# Arc_Reactor_v1_1.net
KiCad netlist of a schematic drawn in EAGLE
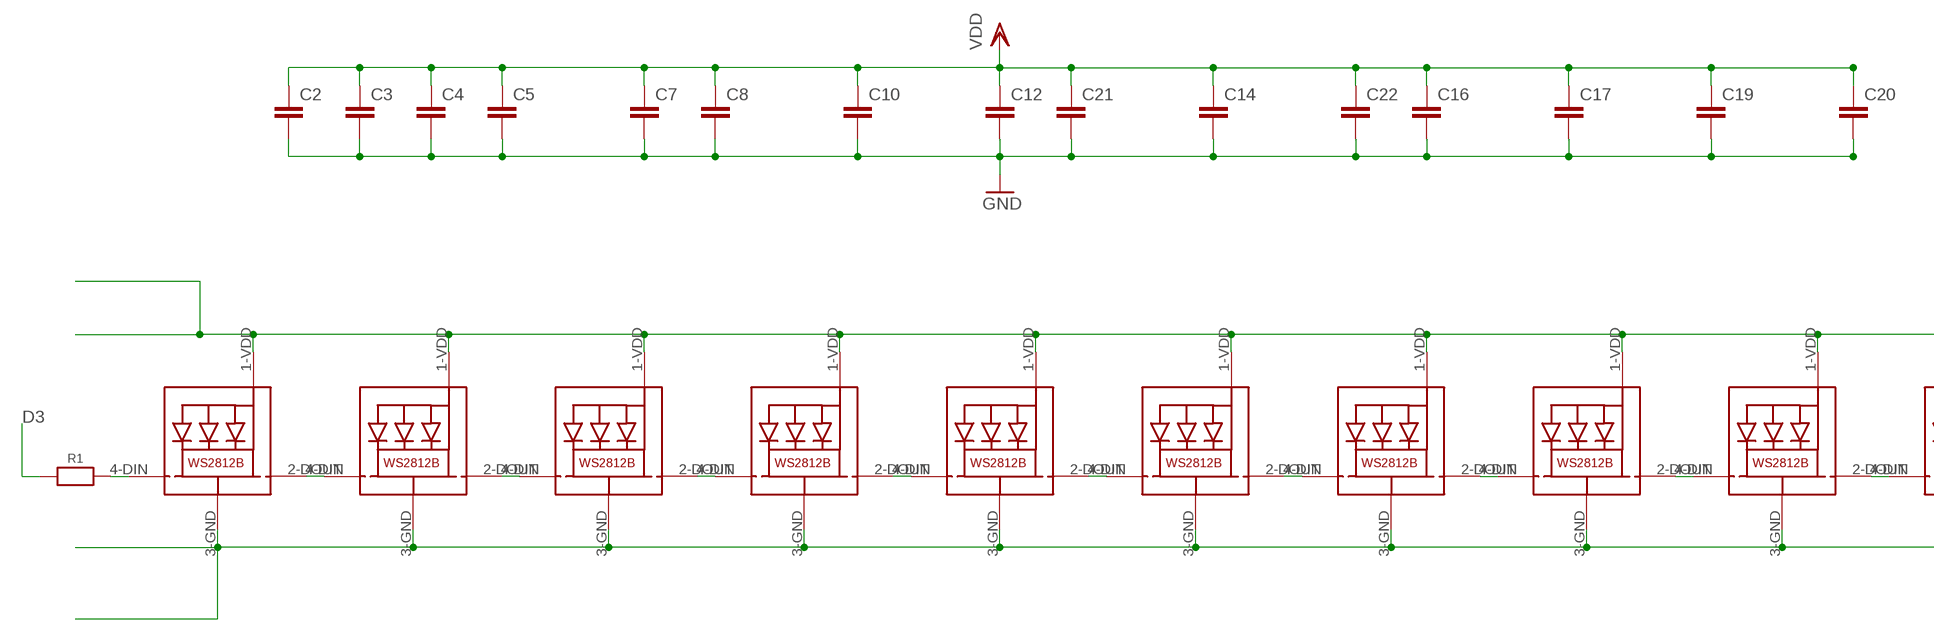
[diagram p0: schematic, sheet 1, part 1 of 2]
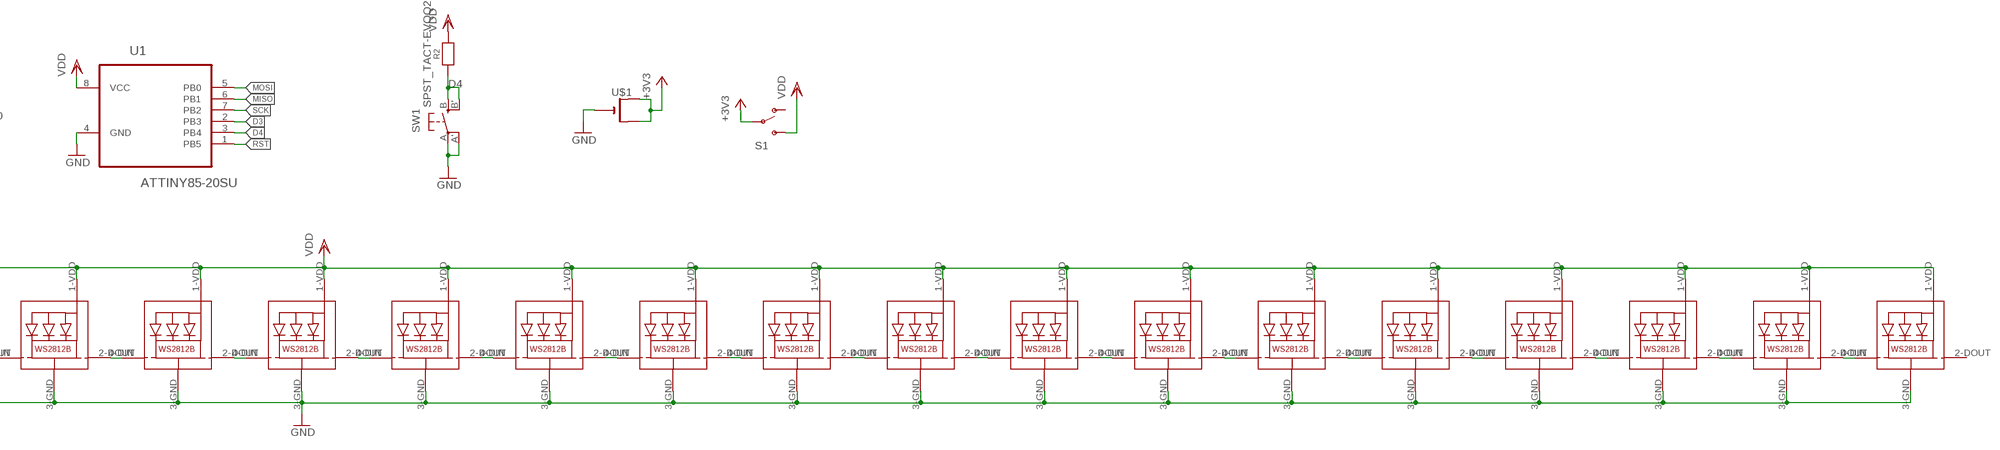
[diagram p1: schematic, sheet 1, part 2 of 2]

(export (version "E")
  (design (tool "Eeschema 10.0.6"))
  (components
    (comp (ref "C2")
      (value "C-EUC0603")
      (footprint "eagle-import:C0603")
      (libsource (lib "eagle-import") (part "C-EUC0603"))
    )
    (comp (ref "C3")
      (value "C-EUC0603")
      (footprint "eagle-import:C0603")
      (libsource (lib "eagle-import") (part "C-EUC0603"))
    )
    (comp (ref "C4")
      (value "C-EUC0603")
      (footprint "eagle-import:C0603")
      (libsource (lib "eagle-import") (part "C-EUC0603"))
    )
    (comp (ref "C5")
      (value "C-EUC0603")
      (footprint "eagle-import:C0603")
      (libsource (lib "eagle-import") (part "C-EUC0603"))
    )
    (comp (ref "C7")
      (value "C-EUC0603")
      (footprint "eagle-import:C0603")
      (libsource (lib "eagle-import") (part "C-EUC0603"))
    )
    (comp (ref "C8")
      (value "C-EUC0603")
      (footprint "eagle-import:C0603")
      (libsource (lib "eagle-import") (part "C-EUC0603"))
    )
    (comp (ref "C10")
      (value "C-EUC0603")
      (footprint "eagle-import:C0603")
      (libsource (lib "eagle-import") (part "C-EUC0603"))
    )
    (comp (ref "C12")
      (value "C-EUC0603")
      (footprint "eagle-import:C0603")
      (libsource (lib "eagle-import") (part "C-EUC0603"))
    )
    (comp (ref "C14")
      (value "C-EUC0603")
      (footprint "eagle-import:C0603")
      (libsource (lib "eagle-import") (part "C-EUC0603"))
    )
    (comp (ref "C16")
      (value "C-EUC0603")
      (footprint "eagle-import:C0603")
      (libsource (lib "eagle-import") (part "C-EUC0603"))
    )
    (comp (ref "C17")
      (value "C-EUC0603")
      (footprint "eagle-import:C0603")
      (libsource (lib "eagle-import") (part "C-EUC0603"))
    )
    (comp (ref "C19")
      (value "C-EUC0603")
      (footprint "eagle-import:C0603")
      (libsource (lib "eagle-import") (part "C-EUC0603"))
    )
    (comp (ref "C20")
      (value "C-EUC0603")
      (footprint "eagle-import:C0603")
      (libsource (lib "eagle-import") (part "C-EUC0603"))
    )
    (comp (ref "C21")
      (value "C-EUC0603")
      (footprint "eagle-import:C0603")
      (libsource (lib "eagle-import") (part "C-EUC0603"))
    )
    (comp (ref "C22")
      (value "C-EUC0603")
      (footprint "eagle-import:C0603")
      (libsource (lib "eagle-import") (part "C-EUC0603"))
    )
    (comp (ref "LED1")
      (value "WS2812B5050")
      (footprint "eagle-import:WS2812B")
      (libsource (lib "eagle-import") (part "WS2812B5050"))
    )
    (comp (ref "LED3")
      (value "WS2812B5050")
      (footprint "eagle-import:WS2812B")
      (libsource (lib "eagle-import") (part "WS2812B5050"))
    )
    (comp (ref "LED4")
      (value "WS2812B5050")
      (footprint "eagle-import:WS2812B")
      (libsource (lib "eagle-import") (part "WS2812B5050"))
    )
    (comp (ref "LED5")
      (value "WS2812B5050")
      (footprint "eagle-import:WS2812B")
      (libsource (lib "eagle-import") (part "WS2812B5050"))
    )
    (comp (ref "LED6")
      (value "WS2812B5050")
      (footprint "eagle-import:WS2812B")
      (libsource (lib "eagle-import") (part "WS2812B5050"))
    )
    (comp (ref "LED7")
      (value "WS2812B5050")
      (footprint "eagle-import:WS2812B")
      (libsource (lib "eagle-import") (part "WS2812B5050"))
    )
    (comp (ref "LED8")
      (value "WS2812B5050")
      (footprint "eagle-import:WS2812B")
      (libsource (lib "eagle-import") (part "WS2812B5050"))
    )
    (comp (ref "LED9")
      (value "WS2812B5050")
      (footprint "eagle-import:WS2812B")
      (libsource (lib "eagle-import") (part "WS2812B5050"))
    )
    (comp (ref "LED10")
      (value "WS2812B5050")
      (footprint "eagle-import:WS2812B")
      (libsource (lib "eagle-import") (part "WS2812B5050"))
    )
    (comp (ref "LED11")
      (value "WS2812B5050")
      (footprint "eagle-import:WS2812B")
      (libsource (lib "eagle-import") (part "WS2812B5050"))
    )
    (comp (ref "LED12")
      (value "WS2812B5050")
      (footprint "eagle-import:WS2812B")
      (libsource (lib "eagle-import") (part "WS2812B5050"))
    )
    (comp (ref "LED13")
      (value "WS2812B5050")
      (footprint "eagle-import:WS2812B")
      (libsource (lib "eagle-import") (part "WS2812B5050"))
    )
    (comp (ref "LED14")
      (value "WS2812B5050")
      (footprint "eagle-import:WS2812B")
      (libsource (lib "eagle-import") (part "WS2812B5050"))
    )
    (comp (ref "LED15")
      (value "WS2812B5050")
      (footprint "eagle-import:WS2812B")
      (libsource (lib "eagle-import") (part "WS2812B5050"))
    )
    (comp (ref "LED16")
      (value "WS2812B5050")
      (footprint "eagle-import:WS2812B")
      (libsource (lib "eagle-import") (part "WS2812B5050"))
    )
    (comp (ref "LED17")
      (value "WS2812B5050")
      (footprint "eagle-import:WS2812B")
      (libsource (lib "eagle-import") (part "WS2812B5050"))
    )
    (comp (ref "LED18")
      (value "WS2812B5050")
      (footprint "eagle-import:WS2812B")
      (libsource (lib "eagle-import") (part "WS2812B5050"))
    )
    (comp (ref "LED19")
      (value "WS2812B5050")
      (footprint "eagle-import:WS2812B")
      (libsource (lib "eagle-import") (part "WS2812B5050"))
    )
    (comp (ref "LED20")
      (value "WS2812B5050")
      (footprint "eagle-import:WS2812B")
      (libsource (lib "eagle-import") (part "WS2812B5050"))
    )
    (comp (ref "LED21")
      (value "WS2812B5050")
      (footprint "eagle-import:WS2812B")
      (libsource (lib "eagle-import") (part "WS2812B5050"))
    )
    (comp (ref "LED22")
      (value "WS2812B5050")
      (footprint "eagle-import:WS2812B")
      (libsource (lib "eagle-import") (part "WS2812B5050"))
    )
    (comp (ref "LED23")
      (value "WS2812B5050")
      (footprint "eagle-import:WS2812B")
      (libsource (lib "eagle-import") (part "WS2812B5050"))
    )
    (comp (ref "LED24")
      (value "WS2812B5050")
      (footprint "eagle-import:WS2812B")
      (libsource (lib "eagle-import") (part "WS2812B5050"))
    )
    (comp (ref "LED25")
      (value "WS2812B5050")
      (footprint "eagle-import:WS2812B")
      (libsource (lib "eagle-import") (part "WS2812B5050"))
    )
    (comp (ref "LED26")
      (value "WS2812B5050")
      (footprint "eagle-import:WS2812B")
      (libsource (lib "eagle-import") (part "WS2812B5050"))
    )
    (comp (ref "R1")
      (value "RESISTOR_0603_NOOUT")
      (footprint "eagle-import:0603-NO")
      (libsource (lib "eagle-import") (part "RESISTOR_0603_NOOUT"))
    )
    (comp (ref "R2")
      (value "RESISTOR_0603_NOOUT")
      (footprint "eagle-import:0603-NO")
      (libsource (lib "eagle-import") (part "RESISTOR_0603_NOOUT"))
    )
    (comp (ref "S1")
      (value "SWITCH-SPDTSMD2")
      (footprint "eagle-import:SWITCH-SPDT-SMD")
      (libsource (lib "eagle-import") (part "SWITCH-SPDTSMD2"))
    )
    (comp (ref "SW1")
      (value "SPST_TACT-EVQQ2")
      (footprint "eagle-import:EVQ-Q2")
      (libsource (lib "eagle-import") (part "SPST_TACT-EVQQ2"))
    )
    (comp (ref "U$1")
      (value "CR2032SMT")
      (footprint "eagle-import:CR2032-SMD")
      (libsource (lib "eagle-import") (part "CR2032SMT"))
    )
    (comp (ref "U1")
      (value "ATTINY85-20SU")
      (footprint "eagle-import:SOIC127P798X216-8N")
      (libsource (lib "eagle-import") (part "ATTINY85-20SU"))
    )
  )
  (nets
    (net (code "1") (name "+3V3") (class "Default")
      (node (ref "S1") (pin "2") (pinfunction "P_2") (pintype "passive"))
      (node (ref "U$1") (pin "+$1") (pinfunction "+_+$1") (pintype "passive"))
      (node (ref "U$1") (pin "+$2") (pinfunction "+1_+$2") (pintype "passive"))
    )
    (net (code "2") (name "D3") (class "Default")
      (node (ref "R1") (pin "1") (pinfunction "1_1") (pintype "passive"))
      (node (ref "U1") (pin "2") (pinfunction "PB3_2") (pintype "bidirectional"))
    )
    (net (code "3") (name "D4") (class "Default")
      (node (ref "R2") (pin "1") (pinfunction "1_1") (pintype "passive"))
      (node (ref "SW1") (pin "B") (pinfunction "S_B") (pintype "passive"))
      (node (ref "SW1") (pin "B'") (pinfunction "S1_B'") (pintype "passive"))
      (node (ref "U1") (pin "3") (pinfunction "PB4_3") (pintype "bidirectional"))
    )
    (net (code "4") (name "GND") (class "Default")
      (node (ref "C10") (pin "2") (pinfunction "2_2") (pintype "passive"))
      (node (ref "C12") (pin "2") (pinfunction "2_2") (pintype "passive"))
      (node (ref "C14") (pin "2") (pinfunction "2_2") (pintype "passive"))
      (node (ref "C16") (pin "2") (pinfunction "2_2") (pintype "passive"))
      (node (ref "C17") (pin "2") (pinfunction "2_2") (pintype "passive"))
      (node (ref "C19") (pin "2") (pinfunction "2_2") (pintype "passive"))
      (node (ref "C2") (pin "2") (pinfunction "2_2") (pintype "passive"))
      (node (ref "C20") (pin "2") (pinfunction "2_2") (pintype "passive"))
      (node (ref "C21") (pin "2") (pinfunction "2_2") (pintype "passive"))
      (node (ref "C22") (pin "2") (pinfunction "2_2") (pintype "passive"))
      (node (ref "C3") (pin "2") (pinfunction "2_2") (pintype "passive"))
      (node (ref "C4") (pin "2") (pinfunction "2_2") (pintype "passive"))
      (node (ref "C5") (pin "2") (pinfunction "2_2") (pintype "passive"))
      (node (ref "C7") (pin "2") (pinfunction "2_2") (pintype "passive"))
      (node (ref "C8") (pin "2") (pinfunction "2_2") (pintype "passive"))
      (node (ref "LED1") (pin "3-GND") (pinfunction "GND_3-GND") (pintype "power_in"))
      (node (ref "LED10") (pin "3-GND") (pinfunction "GND_3-GND") (pintype "power_in"))
      (node (ref "LED11") (pin "3-GND") (pinfunction "GND_3-GND") (pintype "power_in"))
      (node (ref "LED12") (pin "3-GND") (pinfunction "GND_3-GND") (pintype "power_in"))
      (node (ref "LED13") (pin "3-GND") (pinfunction "GND_3-GND") (pintype "power_in"))
      (node (ref "LED14") (pin "3-GND") (pinfunction "GND_3-GND") (pintype "power_in"))
      (node (ref "LED15") (pin "3-GND") (pinfunction "GND_3-GND") (pintype "power_in"))
      (node (ref "LED16") (pin "3-GND") (pinfunction "GND_3-GND") (pintype "power_in"))
      (node (ref "LED17") (pin "3-GND") (pinfunction "GND_3-GND") (pintype "power_in"))
      (node (ref "LED18") (pin "3-GND") (pinfunction "GND_3-GND") (pintype "power_in"))
      (node (ref "LED19") (pin "3-GND") (pinfunction "GND_3-GND") (pintype "power_in"))
      (node (ref "LED20") (pin "3-GND") (pinfunction "GND_3-GND") (pintype "power_in"))
      (node (ref "LED21") (pin "3-GND") (pinfunction "GND_3-GND") (pintype "power_in"))
      (node (ref "LED22") (pin "3-GND") (pinfunction "GND_3-GND") (pintype "power_in"))
      (node (ref "LED23") (pin "3-GND") (pinfunction "GND_3-GND") (pintype "power_in"))
      (node (ref "LED24") (pin "3-GND") (pinfunction "GND_3-GND") (pintype "power_in"))
      (node (ref "LED25") (pin "3-GND") (pinfunction "GND_3-GND") (pintype "power_in"))
      (node (ref "LED26") (pin "3-GND") (pinfunction "GND_3-GND") (pintype "power_in"))
      (node (ref "LED3") (pin "3-GND") (pinfunction "GND_3-GND") (pintype "power_in"))
      (node (ref "LED4") (pin "3-GND") (pinfunction "GND_3-GND") (pintype "power_in"))
      (node (ref "LED5") (pin "3-GND") (pinfunction "GND_3-GND") (pintype "power_in"))
      (node (ref "LED6") (pin "3-GND") (pinfunction "GND_3-GND") (pintype "power_in"))
      (node (ref "LED7") (pin "3-GND") (pinfunction "GND_3-GND") (pintype "power_in"))
      (node (ref "LED8") (pin "3-GND") (pinfunction "GND_3-GND") (pintype "power_in"))
      (node (ref "LED9") (pin "3-GND") (pinfunction "GND_3-GND") (pintype "power_in"))
      (node (ref "SW1") (pin "A") (pinfunction "P_A") (pintype "passive"))
      (node (ref "SW1") (pin "A'") (pinfunction "P1_A'") (pintype "passive"))
      (node (ref "U$1") (pin "-") (pinfunction "-_-") (pintype "passive"))
      (node (ref "U1") (pin "4") (pinfunction "GND_4") (pintype "passive"))
    )
    (net (code "5") (name "MISO") (class "Default")
      (node (ref "U1") (pin "6") (pinfunction "PB1_6") (pintype "bidirectional"))
    )
    (net (code "6") (name "MOSI") (class "Default")
      (node (ref "U1") (pin "5") (pinfunction "PB0_5") (pintype "bidirectional"))
    )
    (net (code "7") (name "Net-(LED1-DI)") (class "Default")
      (node (ref "LED1") (pin "4-DIN") (pinfunction "DI_4-DIN") (pintype "input"))
      (node (ref "R1") (pin "2") (pinfunction "2_2") (pintype "passive"))
    )
    (net (code "8") (name "Net-(LED1-DO)") (class "Default")
      (node (ref "LED1") (pin "2-DOUT") (pinfunction "DO_2-DOUT") (pintype "output"))
      (node (ref "LED3") (pin "4-DIN") (pinfunction "DI_4-DIN") (pintype "input"))
    )
    (net (code "9") (name "Net-(LED3-DO)") (class "Default")
      (node (ref "LED3") (pin "2-DOUT") (pinfunction "DO_2-DOUT") (pintype "output"))
      (node (ref "LED4") (pin "4-DIN") (pinfunction "DI_4-DIN") (pintype "input"))
    )
    (net (code "10") (name "Net-(LED4-DO)") (class "Default")
      (node (ref "LED4") (pin "2-DOUT") (pinfunction "DO_2-DOUT") (pintype "output"))
      (node (ref "LED5") (pin "4-DIN") (pinfunction "DI_4-DIN") (pintype "input"))
    )
    (net (code "11") (name "Net-(LED5-DO)") (class "Default")
      (node (ref "LED5") (pin "2-DOUT") (pinfunction "DO_2-DOUT") (pintype "output"))
      (node (ref "LED6") (pin "4-DIN") (pinfunction "DI_4-DIN") (pintype "input"))
    )
    (net (code "12") (name "Net-(LED6-DO)") (class "Default")
      (node (ref "LED6") (pin "2-DOUT") (pinfunction "DO_2-DOUT") (pintype "output"))
      (node (ref "LED7") (pin "4-DIN") (pinfunction "DI_4-DIN") (pintype "input"))
    )
    (net (code "13") (name "Net-(LED7-DO)") (class "Default")
      (node (ref "LED7") (pin "2-DOUT") (pinfunction "DO_2-DOUT") (pintype "output"))
      (node (ref "LED8") (pin "4-DIN") (pinfunction "DI_4-DIN") (pintype "input"))
    )
    (net (code "14") (name "Net-(LED8-DO)") (class "Default")
      (node (ref "LED8") (pin "2-DOUT") (pinfunction "DO_2-DOUT") (pintype "output"))
      (node (ref "LED9") (pin "4-DIN") (pinfunction "DI_4-DIN") (pintype "input"))
    )
    (net (code "15") (name "Net-(LED10-DI)") (class "Default")
      (node (ref "LED10") (pin "4-DIN") (pinfunction "DI_4-DIN") (pintype "input"))
      (node (ref "LED9") (pin "2-DOUT") (pinfunction "DO_2-DOUT") (pintype "output"))
    )
    (net (code "16") (name "Net-(LED10-DO)") (class "Default")
      (node (ref "LED10") (pin "2-DOUT") (pinfunction "DO_2-DOUT") (pintype "output"))
      (node (ref "LED11") (pin "4-DIN") (pinfunction "DI_4-DIN") (pintype "input"))
    )
    (net (code "17") (name "Net-(LED11-DO)") (class "Default")
      (node (ref "LED11") (pin "2-DOUT") (pinfunction "DO_2-DOUT") (pintype "output"))
      (node (ref "LED12") (pin "4-DIN") (pinfunction "DI_4-DIN") (pintype "input"))
    )
    (net (code "18") (name "Net-(LED12-DO)") (class "Default")
      (node (ref "LED12") (pin "2-DOUT") (pinfunction "DO_2-DOUT") (pintype "output"))
      (node (ref "LED13") (pin "4-DIN") (pinfunction "DI_4-DIN") (pintype "input"))
    )
    (net (code "19") (name "Net-(LED13-DO)") (class "Default")
      (node (ref "LED13") (pin "2-DOUT") (pinfunction "DO_2-DOUT") (pintype "output"))
      (node (ref "LED14") (pin "4-DIN") (pinfunction "DI_4-DIN") (pintype "input"))
    )
    (net (code "20") (name "Net-(LED14-DO)") (class "Default")
      (node (ref "LED14") (pin "2-DOUT") (pinfunction "DO_2-DOUT") (pintype "output"))
      (node (ref "LED15") (pin "4-DIN") (pinfunction "DI_4-DIN") (pintype "input"))
    )
    (net (code "21") (name "Net-(LED15-DO)") (class "Default")
      (node (ref "LED15") (pin "2-DOUT") (pinfunction "DO_2-DOUT") (pintype "output"))
      (node (ref "LED16") (pin "4-DIN") (pinfunction "DI_4-DIN") (pintype "input"))
    )
    (net (code "22") (name "Net-(LED16-DO)") (class "Default")
      (node (ref "LED16") (pin "2-DOUT") (pinfunction "DO_2-DOUT") (pintype "output"))
      (node (ref "LED17") (pin "4-DIN") (pinfunction "DI_4-DIN") (pintype "input"))
    )
    (net (code "23") (name "Net-(LED17-DO)") (class "Default")
      (node (ref "LED17") (pin "2-DOUT") (pinfunction "DO_2-DOUT") (pintype "output"))
      (node (ref "LED18") (pin "4-DIN") (pinfunction "DI_4-DIN") (pintype "input"))
    )
    (net (code "24") (name "Net-(LED18-DO)") (class "Default")
      (node (ref "LED18") (pin "2-DOUT") (pinfunction "DO_2-DOUT") (pintype "output"))
      (node (ref "LED19") (pin "4-DIN") (pinfunction "DI_4-DIN") (pintype "input"))
    )
    (net (code "25") (name "Net-(LED19-DO)") (class "Default")
      (node (ref "LED19") (pin "2-DOUT") (pinfunction "DO_2-DOUT") (pintype "output"))
      (node (ref "LED20") (pin "4-DIN") (pinfunction "DI_4-DIN") (pintype "input"))
    )
    (net (code "26") (name "Net-(LED20-DO)") (class "Default")
      (node (ref "LED20") (pin "2-DOUT") (pinfunction "DO_2-DOUT") (pintype "output"))
      (node (ref "LED21") (pin "4-DIN") (pinfunction "DI_4-DIN") (pintype "input"))
    )
    (net (code "27") (name "Net-(LED21-DO)") (class "Default")
      (node (ref "LED21") (pin "2-DOUT") (pinfunction "DO_2-DOUT") (pintype "output"))
      (node (ref "LED22") (pin "4-DIN") (pinfunction "DI_4-DIN") (pintype "input"))
    )
    (net (code "28") (name "Net-(LED22-DO)") (class "Default")
      (node (ref "LED22") (pin "2-DOUT") (pinfunction "DO_2-DOUT") (pintype "output"))
      (node (ref "LED23") (pin "4-DIN") (pinfunction "DI_4-DIN") (pintype "input"))
    )
    (net (code "29") (name "Net-(LED23-DO)") (class "Default")
      (node (ref "LED23") (pin "2-DOUT") (pinfunction "DO_2-DOUT") (pintype "output"))
      (node (ref "LED24") (pin "4-DIN") (pinfunction "DI_4-DIN") (pintype "input"))
    )
    (net (code "30") (name "Net-(LED24-DO)") (class "Default")
      (node (ref "LED24") (pin "2-DOUT") (pinfunction "DO_2-DOUT") (pintype "output"))
      (node (ref "LED25") (pin "4-DIN") (pinfunction "DI_4-DIN") (pintype "input"))
    )
    (net (code "31") (name "Net-(LED25-DO)") (class "Default")
      (node (ref "LED25") (pin "2-DOUT") (pinfunction "DO_2-DOUT") (pintype "output"))
      (node (ref "LED26") (pin "4-DIN") (pinfunction "DI_4-DIN") (pintype "input"))
    )
    (net (code "32") (name "RST") (class "Default")
      (node (ref "U1") (pin "1") (pinfunction "PB5_1") (pintype "bidirectional"))
    )
    (net (code "33") (name "SCK") (class "Default")
      (node (ref "U1") (pin "7") (pinfunction "PB2_7") (pintype "bidirectional"))
    )
    (net (code "34") (name "VDD") (class "Default")
      (node (ref "C10") (pin "1") (pinfunction "1_1") (pintype "passive"))
      (node (ref "C12") (pin "1") (pinfunction "1_1") (pintype "passive"))
      (node (ref "C14") (pin "1") (pinfunction "1_1") (pintype "passive"))
      (node (ref "C16") (pin "1") (pinfunction "1_1") (pintype "passive"))
      (node (ref "C17") (pin "1") (pinfunction "1_1") (pintype "passive"))
      (node (ref "C19") (pin "1") (pinfunction "1_1") (pintype "passive"))
      (node (ref "C2") (pin "1") (pinfunction "1_1") (pintype "passive"))
      (node (ref "C20") (pin "1") (pinfunction "1_1") (pintype "passive"))
      (node (ref "C21") (pin "1") (pinfunction "1_1") (pintype "passive"))
      (node (ref "C22") (pin "1") (pinfunction "1_1") (pintype "passive"))
      (node (ref "C3") (pin "1") (pinfunction "1_1") (pintype "passive"))
      (node (ref "C4") (pin "1") (pinfunction "1_1") (pintype "passive"))
      (node (ref "C5") (pin "1") (pinfunction "1_1") (pintype "passive"))
      (node (ref "C7") (pin "1") (pinfunction "1_1") (pintype "passive"))
      (node (ref "C8") (pin "1") (pinfunction "1_1") (pintype "passive"))
      (node (ref "LED1") (pin "1-VDD") (pinfunction "VDD_1-VDD") (pintype "power_in"))
      (node (ref "LED10") (pin "1-VDD") (pinfunction "VDD_1-VDD") (pintype "power_in"))
      (node (ref "LED11") (pin "1-VDD") (pinfunction "VDD_1-VDD") (pintype "power_in"))
      (node (ref "LED12") (pin "1-VDD") (pinfunction "VDD_1-VDD") (pintype "power_in"))
      (node (ref "LED13") (pin "1-VDD") (pinfunction "VDD_1-VDD") (pintype "power_in"))
      (node (ref "LED14") (pin "1-VDD") (pinfunction "VDD_1-VDD") (pintype "power_in"))
      (node (ref "LED15") (pin "1-VDD") (pinfunction "VDD_1-VDD") (pintype "power_in"))
      (node (ref "LED16") (pin "1-VDD") (pinfunction "VDD_1-VDD") (pintype "power_in"))
      (node (ref "LED17") (pin "1-VDD") (pinfunction "VDD_1-VDD") (pintype "power_in"))
      (node (ref "LED18") (pin "1-VDD") (pinfunction "VDD_1-VDD") (pintype "power_in"))
      (node (ref "LED19") (pin "1-VDD") (pinfunction "VDD_1-VDD") (pintype "power_in"))
      (node (ref "LED20") (pin "1-VDD") (pinfunction "VDD_1-VDD") (pintype "power_in"))
      (node (ref "LED21") (pin "1-VDD") (pinfunction "VDD_1-VDD") (pintype "power_in"))
      (node (ref "LED22") (pin "1-VDD") (pinfunction "VDD_1-VDD") (pintype "power_in"))
      (node (ref "LED23") (pin "1-VDD") (pinfunction "VDD_1-VDD") (pintype "power_in"))
      (node (ref "LED24") (pin "1-VDD") (pinfunction "VDD_1-VDD") (pintype "power_in"))
      (node (ref "LED25") (pin "1-VDD") (pinfunction "VDD_1-VDD") (pintype "power_in"))
      (node (ref "LED26") (pin "1-VDD") (pinfunction "VDD_1-VDD") (pintype "power_in"))
      (node (ref "LED3") (pin "1-VDD") (pinfunction "VDD_1-VDD") (pintype "power_in"))
      (node (ref "LED4") (pin "1-VDD") (pinfunction "VDD_1-VDD") (pintype "power_in"))
      (node (ref "LED5") (pin "1-VDD") (pinfunction "VDD_1-VDD") (pintype "power_in"))
      (node (ref "LED6") (pin "1-VDD") (pinfunction "VDD_1-VDD") (pintype "power_in"))
      (node (ref "LED7") (pin "1-VDD") (pinfunction "VDD_1-VDD") (pintype "power_in"))
      (node (ref "LED8") (pin "1-VDD") (pinfunction "VDD_1-VDD") (pintype "power_in"))
      (node (ref "LED9") (pin "1-VDD") (pinfunction "VDD_1-VDD") (pintype "power_in"))
      (node (ref "R2") (pin "2") (pinfunction "2_2") (pintype "passive"))
      (node (ref "S1") (pin "3") (pinfunction "S_3") (pintype "passive"))
      (node (ref "U1") (pin "8") (pinfunction "VCC_8") (pintype "power_in"))
    )
    (net (code "35") (name "unconnected-(LED26-DO-Pad2-DOUT)") (class "Default")
      (node (ref "LED26") (pin "2-DOUT") (pinfunction "DO_2-DOUT") (pintype "output"))
    )
    (net (code "36") (name "unconnected-(S1-O-Pad1)") (class "Default")
      (node (ref "S1") (pin "1") (pinfunction "O_1") (pintype "passive"))
    )
  )
)
